# schematic.net
KiCad netlist of a schematic drawn in EasyEDA
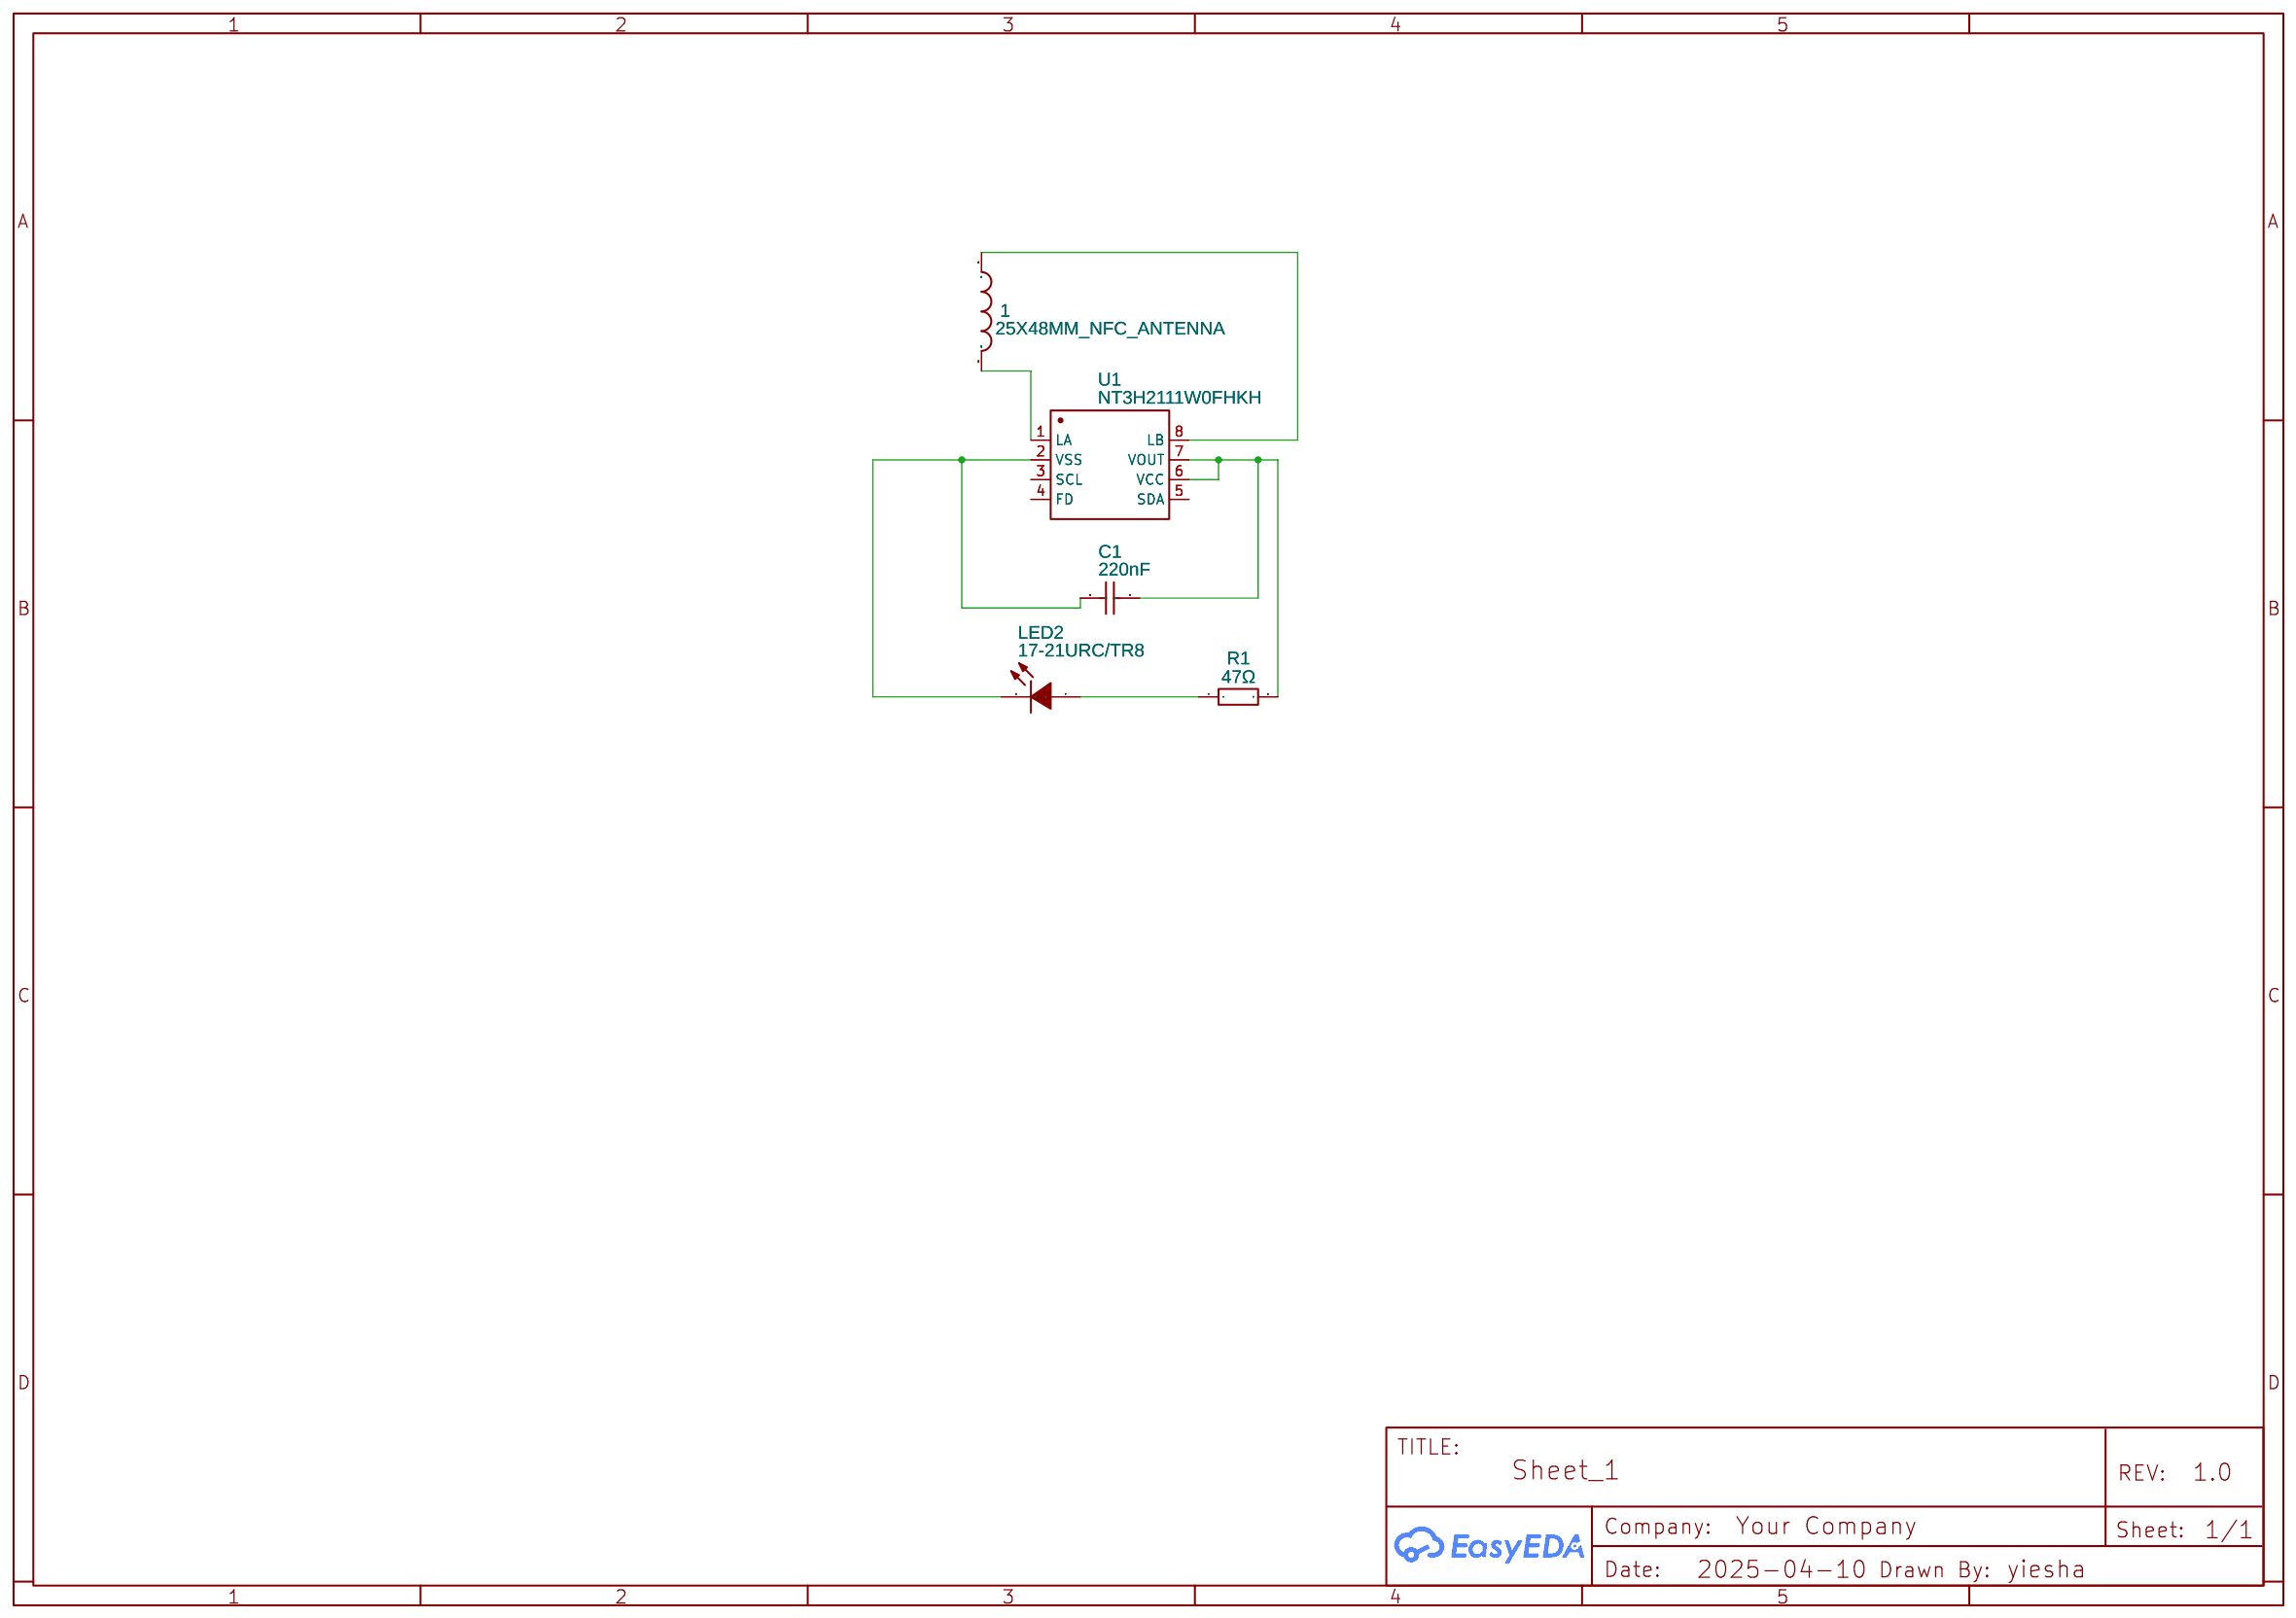
[diagram p0: schematic sheet]

(export (version "E")
  (design (tool "Eeschema 10.0.6"))
  (components
    (comp (ref "1") (value "25X48MM_NFC_ANTENNA") (libsource (lib "") (part "25X48MM_NFC_ANTENNA")))
    (comp (ref "C1")
      (value "220nF")
      (fields
        (field (name "Manufacturer Part") "CL10B224KA8NNNC")
        (field (name "Manufacturer") "SAMSUNG(三星)")
      )
      (libsource (lib "") (part "CL10B224KA8NNNC"))
    )
    (comp (ref "LED2")
      (value "17-21URC/TR8")
      (fields (field (name "Manufacturer") "EVERLIGHT(亿光)"))
      (libsource (lib "") (part "17-21URC/TR8"))
    )
    (comp (ref "R1")
      (value "47Ω")
      (fields
        (field (name "Manufacturer Part") "0603WAF470JT5E")
        (field (name "Manufacturer") "UNI-ROYAL(厚声)")
      )
      (libsource (lib "") (part "0603WAF470JT5E"))
    )
    (comp (ref "U1")
      (value "NT3H2111W0FHKH")
      (fields (field (name "Manufacturer") "NXP(恩智浦)"))
      (libsource (lib "") (part "NT3H2111W0FHKH"))
    )
  )
  (nets
    (net (code "1") (name "Net-(LED2-A)") (class "Default")
      (node (ref "LED2") (pin "1") (pinfunction "A_1") (pintype "unspecified"))
      (node (ref "R1") (pin "1") (pinfunction "1_1") (pintype "input"))
    )
    (net (code "2") (name "Net-(LED2-K)") (class "Default")
      (node (ref "C1") (pin "1") (pinfunction "1_1") (pintype "input"))
      (node (ref "LED2") (pin "2") (pinfunction "K_2") (pintype "unspecified"))
      (node (ref "U1") (pin "2") (pinfunction "VSS_2") (pintype "unspecified"))
    )
    (net (code "3") (name "Net-(U1-LA)") (class "Default")
      (node (ref "1") (pin "P$2") (pinfunction "P$2_P$2") (pintype "bidirectional"))
      (node (ref "U1") (pin "1") (pinfunction "LA_1") (pintype "unspecified"))
    )
    (net (code "4") (name "Net-(U1-LB)") (class "Default")
      (node (ref "1") (pin "P$1") (pinfunction "P$1_P$1") (pintype "bidirectional"))
      (node (ref "U1") (pin "8") (pinfunction "LB_8") (pintype "unspecified"))
    )
    (net (code "5") (name "Net-(U1-VCC)") (class "Default")
      (node (ref "C1") (pin "2") (pinfunction "2_2") (pintype "input"))
      (node (ref "R1") (pin "2") (pinfunction "2_2") (pintype "input"))
      (node (ref "U1") (pin "6") (pinfunction "VCC_6") (pintype "unspecified"))
      (node (ref "U1") (pin "7") (pinfunction "VOUT_7") (pintype "unspecified"))
    )
    (net (code "6") (name "unconnected-(U1-FD-Pad4)") (class "Default")
      (node (ref "U1") (pin "4") (pinfunction "FD_4") (pintype "unspecified"))
    )
    (net (code "7") (name "unconnected-(U1-SCL-Pad3)") (class "Default")
      (node (ref "U1") (pin "3") (pinfunction "SCL_3") (pintype "unspecified"))
    )
    (net (code "8") (name "unconnected-(U1-SDA-Pad5)") (class "Default")
      (node (ref "U1") (pin "5") (pinfunction "SDA_5") (pintype "unspecified"))
    )
  )
)
